# AnalogSensors.net
KiCad netlist of a schematic drawn in Altium Designer
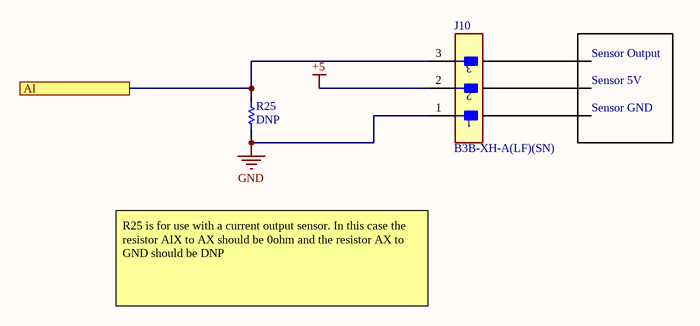
[diagram p0: AnalogSensors.SchDoc]

(export (version "E")
  (design (tool "Eeschema 10.0.6"))
  (components
    (comp (ref "J10")
      (value "B3B-XH-A(LF)(SN)")
      (footprint "FP-B3B-XH-A_LF_SN-MFG")
      (description "CONN HEADER VERT 3POS 2.5MM")
      (fields
        (field (name "OCTOPART") "https://octopart.com/b3b-xh-a%28lf%29%28sn%29-jst-3990185")
        (field (name "MANUFACTURER") "JST")
      )
      (libsource (lib "Altium Content Vault") (part "0d3f023dd272f625e17a2be33dea85f"))
    )
    (comp (ref "R25")
      (value "DNP")
      (footprint "RESC0603(1608)_L")
      (description "249R 0.1W 1% 0603 (1608 Metric)  SMD")
      (fields (field (name "TOLERANCE") "1 %") (field (name "POWER") "0.1 W"))
      (libsource (lib "Altium Content Vault") (part "RES"))
    )
  )
  (nets
    (net (code "1") (name "+5") (class "Default")
      (node (ref "J10") (pin "2") (pinfunction "2_2") (pintype "passive"))
    )
    (net (code "2") (name "/AI") (class "Default")
      (node (ref "J10") (pin "3") (pinfunction "3_3") (pintype "passive"))
      (node (ref "R25") (pin "1") (pinfunction "1_1") (pintype "passive"))
    )
    (net (code "3") (name "GND") (class "Default")
      (node (ref "J10") (pin "1") (pinfunction "1_1") (pintype "passive"))
      (node (ref "R25") (pin "2") (pinfunction "2_2") (pintype "passive"))
    )
  )
)
